# SolBoutout.net
KiCad netlist of a schematic drawn in Altium Designer
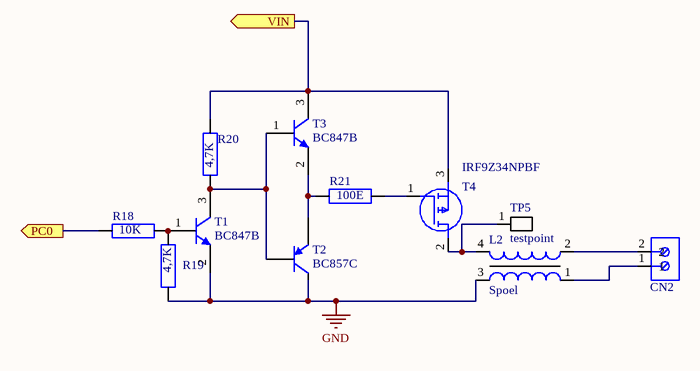
[diagram p0: SolBoutout.SchDoc]

(export (version "E")
  (design (tool "Eeschema 10.0.6"))
  (components
    (comp (ref "CN2")
      (value "282836-2")
      (footprint "cnn2pin")
      (description "Female Header, Pitch 5 mm, 1 x 2 Position, Height 10 mm, Tail Length 3.5 mm, Rohs, Bulk")
      (fields (field (name "VOLTAGE") "300V") (field (name "MANUFACTURER") "TE Connectivity"))
      (libsource (lib "soldeerstation") (part "CNN2P"))
    )
    (comp (ref "L2")
      (value "Spoel")
      (footprint "CoilCM2545")
      (libsource (lib "soldeerstation") (part "Spoel"))
    )
    (comp (ref "R18")
      (value "10K")
      (footprint "res0805ph")
      (description "Resistor")
      (fields (field (name "MANUFACTURER_PART_NUMBER") "CPF0201D10K2C1"))
      (libsource (lib "") (part "Res_1"))
    )
    (comp (ref "R19")
      (value "4,7K")
      (footprint "res0805ph")
      (description "Resistor")
      (fields (field (name "MANUFACTURER_PART_NUMBER") "CPF0201D10K2C1"))
      (libsource (lib "soldeerstation") (part "Res"))
    )
    (comp (ref "R20")
      (value "4,7K")
      (footprint "res0805ph")
      (description "Resistor")
      (fields (field (name "MANUFACTURER_PART_NUMBER") "CPF0201D10K2C1"))
      (libsource (lib "soldeerstation") (part "Res"))
    )
    (comp (ref "R21")
      (value "100E")
      (footprint "res0805ph")
      (description "Resistor")
      (fields (field (name "MANUFACTURER_PART_NUMBER") "CPF0201D10K2C1"))
      (libsource (lib "") (part "Res_2"))
    )
    (comp (ref "T1")
      (value "BC847B")
      (footprint "sot23")
      (description "NPN Silicon AF Transistor, 45 V VCEO, 100 mA IC, SOT23, Reel, Green")
      (fields (field (name "MANUFACTURER") "Infineon"))
      (libsource (lib "soldeerstation") (part "BC847"))
    )
    (comp (ref "T2")
      (value "BC857C")
      (footprint "INF-SOT23_N")
      (description "PNP Silicon AF Transistor, 45 V VCEO, 100 mA IC, SOT23, Reel, Green")
      (fields (field (name "MANUFACTURER") "Infineon"))
      (libsource (lib "Altium Content Vault") (part "INF-BJTPNP-BEC-3"))
    )
    (comp (ref "T3")
      (value "BC847B")
      (footprint "sot23")
      (description "NPN Silicon AF Transistor, 45 V VCEO, 100 mA IC, SOT23, Reel, Green")
      (fields (field (name "MANUFACTURER") "Infineon"))
      (libsource (lib "soldeerstation") (part "BC847"))
    )
    (comp (ref "T4")
      (value "IRF9Z34NPBF")
      (footprint "SamacSys:TO254P469X1042X1967-3P")
      (description "MOSFET (P-Channel)")
      (fields (field (name "MOUSER PART NUMBER") "942-IRF9Z34NPBF"))
      (libsource (lib "soldeerstation") (part "IRF9Z34NPBF"))
    )
    (comp (ref "TP5")
      (value "testpoint")
      (footprint "testpin")
      (libsource (lib "soldeerstation") (part "testpoint"))
    )
  )
  (nets
    (net (code "1") (name "/PC0") (class "Default")
      (node (ref "R18") (pin "1") (pinfunction "1_1") (pintype "passive"))
    )
    (net (code "2") (name "/VIN") (class "Default")
      (node (ref "R20") (pin "1") (pinfunction "1_1") (pintype "passive"))
      (node (ref "T3") (pin "3") (pinfunction "C_3") (pintype "passive"))
      (node (ref "T4") (pin "3") (pinfunction "S_3") (pintype "passive"))
    )
    (net (code "3") (name "GND") (class "Default")
      (node (ref "L2") (pin "3") (pinfunction "3_3") (pintype "passive"))
      (node (ref "R19") (pin "2") (pinfunction "2_2") (pintype "passive"))
      (node (ref "T1") (pin "2") (pinfunction "E_2") (pintype "passive"))
      (node (ref "T2") (pin "3") (pinfunction "C_3") (pintype "passive"))
    )
    (net (code "4") (name "Net-(CN2-Pad1)") (class "Default")
      (node (ref "CN2") (pin "1") (pinfunction "1_1") (pintype "passive"))
      (node (ref "L2") (pin "1") (pinfunction "1_1") (pintype "passive"))
    )
    (net (code "5") (name "Net-(CN2-Pad2)") (class "Default")
      (node (ref "CN2") (pin "2") (pinfunction "2_2") (pintype "passive"))
      (node (ref "L2") (pin "2") (pinfunction "2_2") (pintype "passive"))
    )
    (net (code "6") (name "Net-(T1-B)") (class "Default")
      (node (ref "R18") (pin "2") (pinfunction "2_2") (pintype "passive"))
      (node (ref "R19") (pin "1") (pinfunction "1_1") (pintype "passive"))
      (node (ref "T1") (pin "1") (pinfunction "B_1") (pintype "passive"))
    )
    (net (code "7") (name "Net-(T1-C)") (class "Default")
      (node (ref "R20") (pin "2") (pinfunction "2_2") (pintype "passive"))
      (node (ref "T1") (pin "3") (pinfunction "C_3") (pintype "passive"))
      (node (ref "T2") (pin "1") (pinfunction "B_1") (pintype "passive"))
      (node (ref "T3") (pin "1") (pinfunction "B_1") (pintype "passive"))
    )
    (net (code "8") (name "Net-(T2-E)") (class "Default")
      (node (ref "R21") (pin "2") (pinfunction "2_2") (pintype "passive"))
      (node (ref "T2") (pin "2") (pinfunction "E_2") (pintype "passive"))
      (node (ref "T3") (pin "2") (pinfunction "E_2") (pintype "passive"))
    )
    (net (code "9") (name "Net-(T4-D)") (class "Default")
      (node (ref "L2") (pin "4") (pinfunction "4_4") (pintype "passive"))
      (node (ref "T4") (pin "2") (pinfunction "D_2") (pintype "passive"))
      (node (ref "TP5") (pin "1") (pinfunction "TP_1") (pintype "passive"))
    )
    (net (code "10") (name "Net-(T4-G)") (class "Default")
      (node (ref "R21") (pin "1") (pinfunction "1_1") (pintype "passive"))
      (node (ref "T4") (pin "1") (pinfunction "G_1") (pintype "passive"))
    )
  )
)
